# murdock_mcu_v2.net
KiCad netlist of a schematic drawn in EAGLE
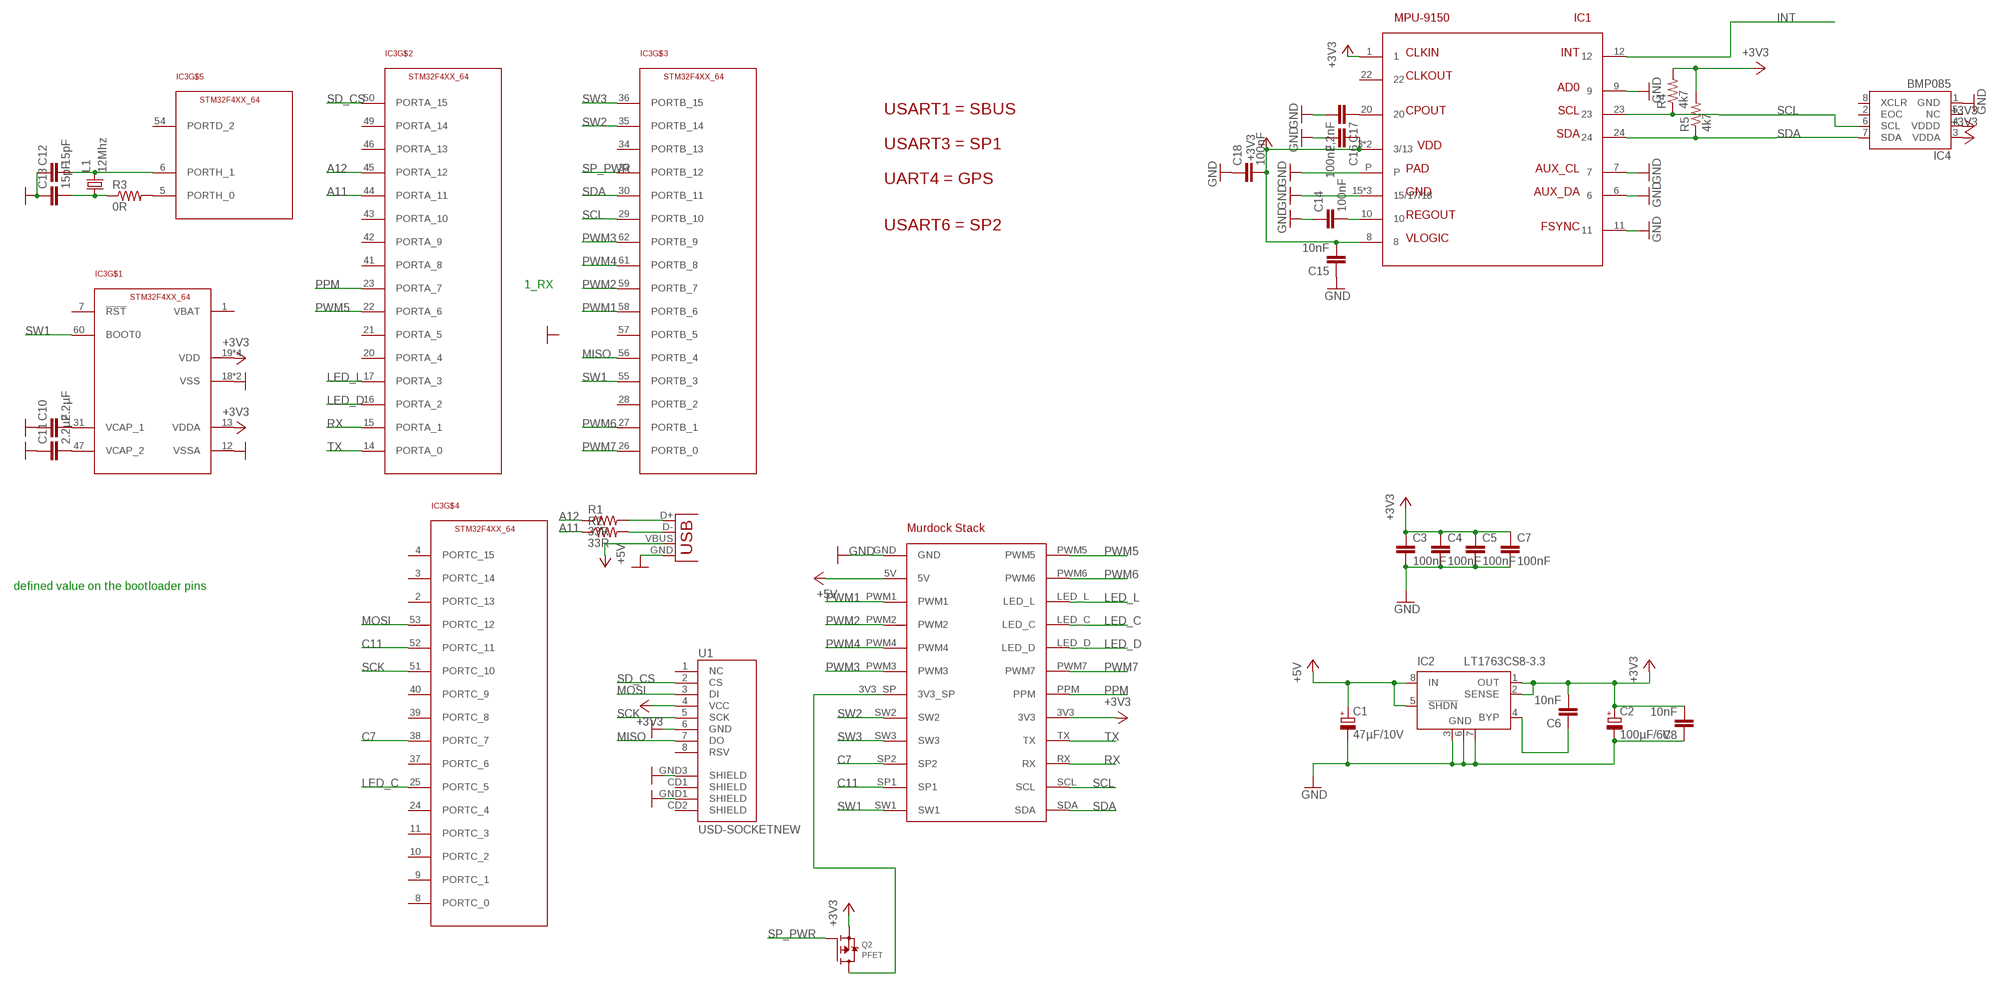
[diagram p0: schematic, sheet 1]

(export (version "E")
  (design (tool "Eeschema 10.0.6"))
  (components
    (comp (ref "C1")
      (value "47µF/10V")
      (footprint "eagle-import:SMC_D")
      (libsource (lib "eagle-import") (part "CPOL-EUSMCD"))
    )
    (comp (ref "C2")
      (value "100µF/6V")
      (footprint "eagle-import:SMC_D")
      (libsource (lib "eagle-import") (part "CPOL-EUSMCD"))
    )
    (comp (ref "C3")
      (value "100nF")
      (footprint "eagle-import:0402-CAP")
      (libsource (lib "eagle-import") (part "SparkFun-Capacitors_CAP0402-CAP"))
    )
    (comp (ref "C4")
      (value "100nF")
      (footprint "eagle-import:0402-CAP")
      (libsource (lib "eagle-import") (part "SparkFun-Capacitors_CAP0402-CAP"))
    )
    (comp (ref "C5")
      (value "100nF")
      (footprint "eagle-import:0402-CAP")
      (libsource (lib "eagle-import") (part "SparkFun-Capacitors_CAP0402-CAP"))
    )
    (comp (ref "C6")
      (value "10nF")
      (footprint "eagle-import:C0402")
      (libsource (lib "eagle-import") (part "C-EUC0402"))
    )
    (comp (ref "C7")
      (value "100nF")
      (footprint "eagle-import:0402-CAP")
      (libsource (lib "eagle-import") (part "SparkFun-Capacitors_CAP0402-CAP"))
    )
    (comp (ref "C8")
      (value "10nF")
      (footprint "eagle-import:C0402")
      (libsource (lib "eagle-import") (part "C-EUC0402"))
    )
    (comp (ref "C10")
      (value "2.2µF")
      (footprint "eagle-import:0805")
      (libsource (lib "eagle-import") (part "SparkFun-Capacitors_CAP0805"))
    )
    (comp (ref "C11")
      (value "2.2µF")
      (footprint "eagle-import:0805")
      (libsource (lib "eagle-import") (part "SparkFun-Capacitors_CAP0805"))
    )
    (comp (ref "C12")
      (value "15pF")
      (footprint "eagle-import:0402-CAP")
      (libsource (lib "eagle-import") (part "SparkFun-Capacitors_CAP0402-CAP"))
    )
    (comp (ref "C13")
      (value "15pF")
      (footprint "eagle-import:0402-CAP")
      (libsource (lib "eagle-import") (part "SparkFun-Capacitors_CAP0402-CAP"))
    )
    (comp (ref "C14")
      (value "100nF")
      (footprint "eagle-import:0402-CAP")
      (libsource (lib "eagle-import") (part "CAP0402-CAP"))
    )
    (comp (ref "C15")
      (value "10nF")
      (footprint "eagle-import:0402-CAP")
      (libsource (lib "eagle-import") (part "CAP0402-CAP"))
    )
    (comp (ref "C16")
      (value "100nF")
      (footprint "eagle-import:0402-CAP")
      (libsource (lib "eagle-import") (part "CAP0402-CAP"))
    )
    (comp (ref "C17")
      (value "2,2nF")
      (footprint "eagle-import:0402-CAP")
      (libsource (lib "eagle-import") (part "CAP0402-CAP"))
    )
    (comp (ref "C18")
      (value "100nF")
      (footprint "eagle-import:0402-CAP")
      (libsource (lib "eagle-import") (part "CAP0402-CAP"))
    )
    (comp (ref "IC1")
      (value "MPU-9150")
      (footprint "eagle-import:QFN24")
      (libsource (lib "eagle-import") (part "MPU-9150"))
    )
    (comp (ref "IC2")
      (value "LT1763CS8-3.3")
      (footprint "eagle-import:SOIC8")
      (libsource (lib "eagle-import") (part "LT1763CS8-3.3"))
    )
    (comp (ref "IC3")
      (value "STM32F4XX_64")
      (footprint "eagle-import:TQFP64")
      (libsource (lib "eagle-import") (part "STM32F4XX_64"))
    )
    (comp (ref "IC4")
      (value "BMP085")
      (footprint "eagle-import:BMP085")
      (libsource (lib "eagle-import") (part "BMP085"))
    )
    (comp (ref "L1")
      (value "12Mhz")
      (footprint "eagle-import:X22")
      (libsource (lib "eagle-import") (part "X22-OSCILLATOR"))
    )
    (comp (ref "Q2")
      (value "PFET")
      (footprint "eagle-import:SOT23-R")
      (libsource (lib "eagle-import") (part "MOSFET-P"))
    )
    (comp (ref "R1")
      (value "33R")
      (footprint "eagle-import:0402-RES")
      (libsource (lib "eagle-import") (part "SparkFun-Resistors_RESISTOR0402-RES"))
    )
    (comp (ref "R2")
      (value "33R")
      (footprint "eagle-import:0402-RES")
      (libsource (lib "eagle-import") (part "SparkFun-Resistors_RESISTOR0402-RES"))
    )
    (comp (ref "R3")
      (value "0R")
      (footprint "eagle-import:0402-RES")
      (libsource (lib "eagle-import") (part "SparkFun-Resistors_RESISTOR0402-RES"))
    )
    (comp (ref "R4")
      (value "4k7")
      (footprint "eagle-import:0402-RES")
      (libsource (lib "eagle-import") (part "RESISTOR0402-RES"))
    )
    (comp (ref "R5")
      (value "4k7")
      (footprint "eagle-import:0402-RES")
      (libsource (lib "eagle-import") (part "RESISTOR0402-RES"))
    )
    (comp (ref "U1")
      (value "USD-SOCKETNEW")
      (footprint "eagle-import:MICRO-SD-SOCKET-PP")
      (libsource (lib "eagle-import") (part "USD-SOCKETNEW"))
    )
    (comp (ref "X1")
      (value "USBSMD")
      (footprint "eagle-import:USB-MINIB")
      (libsource (lib "eagle-import") (part "USBSMD"))
    )
    (comp (ref "X2")
      (value "MURDOCK_STACK")
      (footprint "eagle-import:MURDOCK_STACK")
      (libsource (lib "eagle-import") (part "MURDOCK_STACK"))
    )
  )
  (nets
    (net (code "1") (name "+3V3") (class "Default")
      (node (ref "C15") (pin "2") (pinfunction "2_2") (pintype "passive"))
      (node (ref "C16") (pin "1") (pinfunction "1_1") (pintype "passive"))
      (node (ref "C18") (pin "2") (pinfunction "2_2") (pintype "passive"))
      (node (ref "C2") (pin "+") (pinfunction "+_+") (pintype "passive"))
      (node (ref "C3") (pin "1") (pinfunction "1_1") (pintype "passive"))
      (node (ref "C4") (pin "1") (pinfunction "1_1") (pintype "passive"))
      (node (ref "C5") (pin "1") (pinfunction "1_1") (pintype "passive"))
      (node (ref "C6") (pin "2") (pinfunction "2_2") (pintype "passive"))
      (node (ref "C7") (pin "1") (pinfunction "1_1") (pintype "passive"))
      (node (ref "C8") (pin "2") (pinfunction "2_2") (pintype "passive"))
      (node (ref "IC1") (pin "1") (pinfunction "1_1") (pintype "bidirectional"))
      (node (ref "IC1") (pin "13") (pinfunction "3/13_13") (pintype "bidirectional"))
      (node (ref "IC1") (pin "3") (pinfunction "3/13_3") (pintype "bidirectional"))
      (node (ref "IC1") (pin "8") (pinfunction "8_8") (pintype "bidirectional"))
      (node (ref "IC2") (pin "1") (pinfunction "OUT_1") (pintype "passive"))
      (node (ref "IC2") (pin "2") (pinfunction "SENSE_2") (pintype "input"))
      (node (ref "IC3") (pin "13") (pinfunction "VDDA_13") (pintype "bidirectional"))
      (node (ref "IC3") (pin "19") (pinfunction "VDD_19") (pintype "bidirectional"))
      (node (ref "IC3") (pin "32") (pinfunction "VDD_32") (pintype "bidirectional"))
      (node (ref "IC3") (pin "48") (pinfunction "VDD_48") (pintype "bidirectional"))
      (node (ref "IC3") (pin "64") (pinfunction "VDD_64") (pintype "bidirectional"))
      (node (ref "IC4") (pin "3") (pinfunction "VDDA_3") (pintype "power_in"))
      (node (ref "IC4") (pin "4") (pinfunction "VDDD_4") (pintype "power_in"))
      (node (ref "Q2") (pin "2") (pinfunction "S_2") (pintype "passive"))
      (node (ref "R4") (pin "2") (pinfunction "2_2") (pintype "passive"))
      (node (ref "R5") (pin "2") (pinfunction "2_2") (pintype "passive"))
      (node (ref "U1") (pin "4") (pinfunction "VCC_4") (pintype "bidirectional"))
      (node (ref "X2") (pin "3V3") (pinfunction "3V3_3V3") (pintype "bidirectional"))
    )
    (net (code "2") (name "+5V") (class "Default")
      (node (ref "C1") (pin "+") (pinfunction "+_+") (pintype "passive"))
      (node (ref "IC2") (pin "5") (pinfunction "~{SHDN}_5") (pintype "input"))
      (node (ref "IC2") (pin "8") (pinfunction "IN_8") (pintype "input"))
      (node (ref "X1") (pin "VBUS") (pinfunction "VBUS_VBUS") (pintype "bidirectional"))
      (node (ref "X2") (pin "5V") (pinfunction "5V_5V") (pintype "bidirectional"))
    )
    (net (code "3") (name "/A11") (class "Default")
      (node (ref "IC3") (pin "44") (pinfunction "PORTA_11_44") (pintype "bidirectional"))
      (node (ref "R2") (pin "1") (pinfunction "1_1") (pintype "passive"))
    )
    (net (code "4") (name "/A12") (class "Default")
      (node (ref "IC3") (pin "45") (pinfunction "PORTA_12_45") (pintype "bidirectional"))
      (node (ref "R1") (pin "1") (pinfunction "1_1") (pintype "passive"))
    )
    (net (code "5") (name "/C7") (class "Default")
      (node (ref "IC3") (pin "38") (pinfunction "PORTC_7_38") (pintype "bidirectional"))
      (node (ref "X2") (pin "SP2") (pinfunction "SP2_SP2") (pintype "bidirectional"))
    )
    (net (code "6") (name "/C11") (class "Default")
      (node (ref "IC3") (pin "52") (pinfunction "PORTC_11_52") (pintype "bidirectional"))
      (node (ref "X2") (pin "SP1") (pinfunction "SP1_SP1") (pintype "bidirectional"))
    )
    (net (code "7") (name "/INT") (class "Default")
      (node (ref "IC1") (pin "12") (pinfunction "12_12") (pintype "bidirectional"))
    )
    (net (code "8") (name "/LED_C") (class "Default")
      (node (ref "IC3") (pin "25") (pinfunction "PORTC_5_25") (pintype "bidirectional"))
      (node (ref "X2") (pin "LED_C") (pinfunction "LED_C_LED_C") (pintype "bidirectional"))
    )
    (net (code "9") (name "/LED_D") (class "Default")
      (node (ref "IC3") (pin "16") (pinfunction "PORTA_2_16") (pintype "bidirectional"))
      (node (ref "X2") (pin "LED_D") (pinfunction "LED_D_LED_D") (pintype "bidirectional"))
    )
    (net (code "10") (name "/LED_L") (class "Default")
      (node (ref "IC3") (pin "17") (pinfunction "PORTA_3_17") (pintype "bidirectional"))
      (node (ref "X2") (pin "LED_L") (pinfunction "LED_L_LED_L") (pintype "bidirectional"))
    )
    (net (code "11") (name "/MISO") (class "Default")
      (node (ref "IC3") (pin "56") (pinfunction "PORTB_4_56") (pintype "bidirectional"))
      (node (ref "U1") (pin "7") (pinfunction "DO_7") (pintype "bidirectional"))
    )
    (net (code "12") (name "/MOSI") (class "Default")
      (node (ref "IC3") (pin "53") (pinfunction "PORTC_12_53") (pintype "bidirectional"))
      (node (ref "U1") (pin "3") (pinfunction "DI_3") (pintype "bidirectional"))
    )
    (net (code "13") (name "/PPM") (class "Default")
      (node (ref "IC3") (pin "23") (pinfunction "PORTA_7_23") (pintype "bidirectional"))
      (node (ref "X2") (pin "PPM") (pinfunction "PPM_PPM") (pintype "bidirectional"))
    )
    (net (code "14") (name "/PWM1") (class "Default")
      (node (ref "IC3") (pin "58") (pinfunction "PORTB_6_58") (pintype "bidirectional"))
      (node (ref "X2") (pin "PWM1") (pinfunction "PWM1_PWM1") (pintype "bidirectional"))
    )
    (net (code "15") (name "/PWM2") (class "Default")
      (node (ref "IC3") (pin "59") (pinfunction "PORTB_7_59") (pintype "bidirectional"))
      (node (ref "X2") (pin "PWM2") (pinfunction "PWM2_PWM2") (pintype "bidirectional"))
    )
    (net (code "16") (name "/PWM3") (class "Default")
      (node (ref "IC3") (pin "62") (pinfunction "PORTB_9_62") (pintype "bidirectional"))
      (node (ref "X2") (pin "PWM3") (pinfunction "PWM3_PWM3") (pintype "bidirectional"))
    )
    (net (code "17") (name "/PWM4") (class "Default")
      (node (ref "IC3") (pin "61") (pinfunction "PORTB_8_61") (pintype "bidirectional"))
      (node (ref "X2") (pin "PWM4") (pinfunction "PWM4_PWM4") (pintype "bidirectional"))
    )
    (net (code "18") (name "/PWM5") (class "Default")
      (node (ref "IC3") (pin "22") (pinfunction "PORTA_6_22") (pintype "bidirectional"))
      (node (ref "X2") (pin "PWM5") (pinfunction "PWM5_PWM5") (pintype "bidirectional"))
    )
    (net (code "19") (name "/PWM6") (class "Default")
      (node (ref "IC3") (pin "27") (pinfunction "PORTB_1_27") (pintype "bidirectional"))
      (node (ref "X2") (pin "PWM6") (pinfunction "PWM6_PWM6") (pintype "bidirectional"))
    )
    (net (code "20") (name "/PWM7") (class "Default")
      (node (ref "IC3") (pin "26") (pinfunction "PORTB_0_26") (pintype "bidirectional"))
      (node (ref "X2") (pin "PWM7") (pinfunction "PWM7_PWM7") (pintype "bidirectional"))
    )
    (net (code "21") (name "/RX") (class "Default")
      (node (ref "IC3") (pin "15") (pinfunction "PORTA_1_15") (pintype "bidirectional"))
      (node (ref "X2") (pin "RX") (pinfunction "RX_RX") (pintype "bidirectional"))
    )
    (net (code "22") (name "/SCK") (class "Default")
      (node (ref "IC3") (pin "51") (pinfunction "PORTC_10_51") (pintype "bidirectional"))
      (node (ref "U1") (pin "5") (pinfunction "SCK_5") (pintype "bidirectional"))
    )
    (net (code "23") (name "/SCL") (class "Default")
      (node (ref "IC1") (pin "23") (pinfunction "23_23") (pintype "bidirectional"))
      (node (ref "IC3") (pin "29") (pinfunction "PORTB_10_29") (pintype "bidirectional"))
      (node (ref "IC4") (pin "6") (pinfunction "SCL_6") (pintype "input"))
      (node (ref "R4") (pin "1") (pinfunction "1_1") (pintype "passive"))
      (node (ref "X2") (pin "SCL") (pinfunction "SCL_SCL") (pintype "bidirectional"))
    )
    (net (code "24") (name "/SDA") (class "Default")
      (node (ref "IC1") (pin "24") (pinfunction "24_24") (pintype "bidirectional"))
      (node (ref "IC3") (pin "30") (pinfunction "PORTB_11_30") (pintype "bidirectional"))
      (node (ref "IC4") (pin "7") (pinfunction "SDA_7") (pintype "bidirectional"))
      (node (ref "R5") (pin "1") (pinfunction "1_1") (pintype "passive"))
      (node (ref "X2") (pin "SDA") (pinfunction "SDA_SDA") (pintype "bidirectional"))
    )
    (net (code "25") (name "/SD_CS") (class "Default")
      (node (ref "IC3") (pin "50") (pinfunction "PORTA_15_50") (pintype "bidirectional"))
      (node (ref "U1") (pin "2") (pinfunction "CS_2") (pintype "bidirectional"))
    )
    (net (code "26") (name "/SP_PWR") (class "Default")
      (node (ref "IC3") (pin "33") (pinfunction "PORTB_12_33") (pintype "bidirectional"))
      (node (ref "Q2") (pin "1") (pinfunction "G_1") (pintype "passive"))
    )
    (net (code "27") (name "/SW1") (class "Default")
      (node (ref "IC3") (pin "55") (pinfunction "PORTB_3_55") (pintype "bidirectional"))
      (node (ref "IC3") (pin "60") (pinfunction "BOOT0_60") (pintype "bidirectional"))
      (node (ref "X2") (pin "SW1") (pinfunction "SW1_SW1") (pintype "bidirectional"))
    )
    (net (code "28") (name "/SW2") (class "Default")
      (node (ref "IC3") (pin "35") (pinfunction "PORTB_14_35") (pintype "bidirectional"))
      (node (ref "X2") (pin "SW2") (pinfunction "SW2_SW2") (pintype "bidirectional"))
    )
    (net (code "29") (name "/SW3") (class "Default")
      (node (ref "IC3") (pin "36") (pinfunction "PORTB_15_36") (pintype "bidirectional"))
      (node (ref "X2") (pin "SW3") (pinfunction "SW3_SW3") (pintype "bidirectional"))
    )
    (net (code "30") (name "/TX") (class "Default")
      (node (ref "IC3") (pin "14") (pinfunction "PORTA_0_14") (pintype "bidirectional"))
      (node (ref "X2") (pin "TX") (pinfunction "TX_TX") (pintype "bidirectional"))
    )
    (net (code "31") (name "GND") (class "Default")
      (node (ref "C1") (pin "-") (pinfunction "-_-") (pintype "passive"))
      (node (ref "C10") (pin "1") (pinfunction "1_1") (pintype "passive"))
      (node (ref "C11") (pin "1") (pinfunction "1_1") (pintype "passive"))
      (node (ref "C12") (pin "1") (pinfunction "1_1") (pintype "passive"))
      (node (ref "C13") (pin "1") (pinfunction "1_1") (pintype "passive"))
      (node (ref "C14") (pin "1") (pinfunction "1_1") (pintype "passive"))
      (node (ref "C15") (pin "1") (pinfunction "1_1") (pintype "passive"))
      (node (ref "C16") (pin "2") (pinfunction "2_2") (pintype "passive"))
      (node (ref "C17") (pin "2") (pinfunction "2_2") (pintype "passive"))
      (node (ref "C18") (pin "1") (pinfunction "1_1") (pintype "passive"))
      (node (ref "C2") (pin "-") (pinfunction "-_-") (pintype "passive"))
      (node (ref "C3") (pin "2") (pinfunction "2_2") (pintype "passive"))
      (node (ref "C4") (pin "2") (pinfunction "2_2") (pintype "passive"))
      (node (ref "C5") (pin "2") (pinfunction "2_2") (pintype "passive"))
      (node (ref "C7") (pin "2") (pinfunction "2_2") (pintype "passive"))
      (node (ref "C8") (pin "1") (pinfunction "1_1") (pintype "passive"))
      (node (ref "IC1") (pin "11") (pinfunction "11_11") (pintype "bidirectional"))
      (node (ref "IC1") (pin "15") (pinfunction "15/17/18_15") (pintype "bidirectional"))
      (node (ref "IC1") (pin "17") (pinfunction "15/17/18_17") (pintype "bidirectional"))
      (node (ref "IC1") (pin "18") (pinfunction "15/17/18_18") (pintype "bidirectional"))
      (node (ref "IC1") (pin "6") (pinfunction "6_6") (pintype "bidirectional"))
      (node (ref "IC1") (pin "7") (pinfunction "7_7") (pintype "bidirectional"))
      (node (ref "IC1") (pin "9") (pinfunction "9_9") (pintype "bidirectional"))
      (node (ref "IC1") (pin "P") (pinfunction "P_P") (pintype "bidirectional"))
      (node (ref "IC2") (pin "3") (pinfunction "GND_3") (pintype "power_in"))
      (node (ref "IC2") (pin "6") (pinfunction "GND_6") (pintype "power_in"))
      (node (ref "IC2") (pin "7") (pinfunction "GND_7") (pintype "power_in"))
      (node (ref "IC3") (pin "12") (pinfunction "VSSA_12") (pintype "bidirectional"))
      (node (ref "IC3") (pin "18") (pinfunction "VSS_18") (pintype "bidirectional"))
      (node (ref "IC3") (pin "63") (pinfunction "VSS_63") (pintype "bidirectional"))
      (node (ref "IC4") (pin "1") (pinfunction "GND_1") (pintype "power_in"))
      (node (ref "U1") (pin "6") (pinfunction "GND_6") (pintype "bidirectional"))
      (node (ref "U1") (pin "GND1") (pinfunction "SHIELD_GND1") (pintype "bidirectional"))
      (node (ref "U1") (pin "GND3") (pinfunction "SHIELD_GND3") (pintype "bidirectional"))
      (node (ref "X1") (pin "GND") (pinfunction "GND_GND") (pintype "bidirectional"))
      (node (ref "X2") (pin "GND") (pinfunction "GND_GND") (pintype "bidirectional"))
    )
    (net (code "32") (name "Net-(C13-Pad2)") (class "Default")
      (node (ref "C13") (pin "2") (pinfunction "2_2") (pintype "passive"))
      (node (ref "L1") (pin "1") (pinfunction "1_1") (pintype "passive"))
      (node (ref "R3") (pin "1") (pinfunction "1_1") (pintype "passive"))
    )
    (net (code "33") (name "Net-(C14-Pad2)") (class "Default")
      (node (ref "C14") (pin "2") (pinfunction "2_2") (pintype "passive"))
      (node (ref "IC1") (pin "10") (pinfunction "10_10") (pintype "bidirectional"))
    )
    (net (code "34") (name "Net-(C17-Pad1)") (class "Default")
      (node (ref "C17") (pin "1") (pinfunction "1_1") (pintype "passive"))
      (node (ref "IC1") (pin "20") (pinfunction "20_20") (pintype "bidirectional"))
    )
    (net (code "35") (name "Net-(IC2-BYP)") (class "Default")
      (node (ref "C6") (pin "1") (pinfunction "1_1") (pintype "passive"))
      (node (ref "IC2") (pin "4") (pinfunction "BYP_4") (pintype "input"))
    )
    (net (code "36") (name "Net-(IC3A-VCAP_1)") (class "Default")
      (node (ref "C10") (pin "2") (pinfunction "2_2") (pintype "passive"))
      (node (ref "IC3") (pin "31") (pinfunction "VCAP_1_31") (pintype "bidirectional"))
    )
    (net (code "37") (name "Net-(IC3A-VCAP_2)") (class "Default")
      (node (ref "C11") (pin "2") (pinfunction "2_2") (pintype "passive"))
      (node (ref "IC3") (pin "47") (pinfunction "VCAP_2_47") (pintype "bidirectional"))
    )
    (net (code "38") (name "Net-(IC3E-PORTH_0)") (class "Default")
      (node (ref "IC3") (pin "5") (pinfunction "PORTH_0_5") (pintype "bidirectional"))
      (node (ref "R3") (pin "2") (pinfunction "2_2") (pintype "passive"))
    )
    (net (code "39") (name "Net-(IC3E-PORTH_1)") (class "Default")
      (node (ref "C12") (pin "2") (pinfunction "2_2") (pintype "passive"))
      (node (ref "IC3") (pin "6") (pinfunction "PORTH_1_6") (pintype "bidirectional"))
      (node (ref "L1") (pin "3") (pinfunction "2_3") (pintype "passive"))
    )
    (net (code "40") (name "Net-(Q2-D)") (class "Default")
      (node (ref "Q2") (pin "3") (pinfunction "D_3") (pintype "passive"))
      (node (ref "X2") (pin "3V3_SP") (pinfunction "3V3_SP_3V3_SP") (pintype "bidirectional"))
    )
    (net (code "41") (name "Net-(R1-Pad2)") (class "Default")
      (node (ref "R1") (pin "2") (pinfunction "2_2") (pintype "passive"))
      (node (ref "X1") (pin "D+") (pinfunction "D+_D+") (pintype "bidirectional"))
    )
    (net (code "42") (name "Net-(R2-Pad2)") (class "Default")
      (node (ref "R2") (pin "2") (pinfunction "2_2") (pintype "passive"))
      (node (ref "X1") (pin "D-") (pinfunction "D-_D-") (pintype "bidirectional"))
    )
    (net (code "43") (name "unconnected-(IC1-Pad22)") (class "Default")
      (node (ref "IC1") (pin "22") (pinfunction "22_22") (pintype "bidirectional"))
    )
    (net (code "44") (name "unconnected-(IC3A-VBAT-Pad1)") (class "Default")
      (node (ref "IC3") (pin "1") (pinfunction "VBAT_1") (pintype "bidirectional"))
    )
    (net (code "45") (name "unconnected-(IC3A-~{RST}-Pad7)") (class "Default")
      (node (ref "IC3") (pin "7") (pinfunction "~{RST}_7") (pintype "bidirectional"))
    )
    (net (code "46") (name "unconnected-(IC3B-PORTA_4-Pad20)") (class "Default")
      (node (ref "IC3") (pin "20") (pinfunction "PORTA_4_20") (pintype "bidirectional"))
    )
    (net (code "47") (name "unconnected-(IC3B-PORTA_5-Pad21)") (class "Default")
      (node (ref "IC3") (pin "21") (pinfunction "PORTA_5_21") (pintype "bidirectional"))
    )
    (net (code "48") (name "unconnected-(IC3B-PORTA_8-Pad41)") (class "Default")
      (node (ref "IC3") (pin "41") (pinfunction "PORTA_8_41") (pintype "bidirectional"))
    )
    (net (code "49") (name "unconnected-(IC3B-PORTA_9-Pad42)") (class "Default")
      (node (ref "IC3") (pin "42") (pinfunction "PORTA_9_42") (pintype "bidirectional"))
    )
    (net (code "50") (name "unconnected-(IC3B-PORTA_10-Pad43)") (class "Default")
      (node (ref "IC3") (pin "43") (pinfunction "PORTA_10_43") (pintype "bidirectional"))
    )
    (net (code "51") (name "unconnected-(IC3B-PORTA_13-Pad46)") (class "Default")
      (node (ref "IC3") (pin "46") (pinfunction "PORTA_13_46") (pintype "bidirectional"))
    )
    (net (code "52") (name "unconnected-(IC3B-PORTA_14-Pad49)") (class "Default")
      (node (ref "IC3") (pin "49") (pinfunction "PORTA_14_49") (pintype "bidirectional"))
    )
    (net (code "53") (name "unconnected-(IC3C-PORTB_2-Pad28)") (class "Default")
      (node (ref "IC3") (pin "28") (pinfunction "PORTB_2_28") (pintype "bidirectional"))
    )
    (net (code "54") (name "unconnected-(IC3C-PORTB_5-Pad57)") (class "Default")
      (node (ref "IC3") (pin "57") (pinfunction "PORTB_5_57") (pintype "bidirectional"))
    )
    (net (code "55") (name "unconnected-(IC3C-PORTB_13-Pad34)") (class "Default")
      (node (ref "IC3") (pin "34") (pinfunction "PORTB_13_34") (pintype "bidirectional"))
    )
    (net (code "56") (name "unconnected-(IC3D-PORTC_0-Pad8)") (class "Default")
      (node (ref "IC3") (pin "8") (pinfunction "PORTC_0_8") (pintype "bidirectional"))
    )
    (net (code "57") (name "unconnected-(IC3D-PORTC_1-Pad9)") (class "Default")
      (node (ref "IC3") (pin "9") (pinfunction "PORTC_1_9") (pintype "bidirectional"))
    )
    (net (code "58") (name "unconnected-(IC3D-PORTC_2-Pad10)") (class "Default")
      (node (ref "IC3") (pin "10") (pinfunction "PORTC_2_10") (pintype "bidirectional"))
    )
    (net (code "59") (name "unconnected-(IC3D-PORTC_3-Pad11)") (class "Default")
      (node (ref "IC3") (pin "11") (pinfunction "PORTC_3_11") (pintype "bidirectional"))
    )
    (net (code "60") (name "unconnected-(IC3D-PORTC_4-Pad24)") (class "Default")
      (node (ref "IC3") (pin "24") (pinfunction "PORTC_4_24") (pintype "bidirectional"))
    )
    (net (code "61") (name "unconnected-(IC3D-PORTC_6-Pad37)") (class "Default")
      (node (ref "IC3") (pin "37") (pinfunction "PORTC_6_37") (pintype "bidirectional"))
    )
    (net (code "62") (name "unconnected-(IC3D-PORTC_8-Pad39)") (class "Default")
      (node (ref "IC3") (pin "39") (pinfunction "PORTC_8_39") (pintype "bidirectional"))
    )
    (net (code "63") (name "unconnected-(IC3D-PORTC_9-Pad40)") (class "Default")
      (node (ref "IC3") (pin "40") (pinfunction "PORTC_9_40") (pintype "bidirectional"))
    )
    (net (code "64") (name "unconnected-(IC3D-PORTC_13-Pad2)") (class "Default")
      (node (ref "IC3") (pin "2") (pinfunction "PORTC_13_2") (pintype "bidirectional"))
    )
    (net (code "65") (name "unconnected-(IC3D-PORTC_14-Pad3)") (class "Default")
      (node (ref "IC3") (pin "3") (pinfunction "PORTC_14_3") (pintype "bidirectional"))
    )
    (net (code "66") (name "unconnected-(IC3D-PORTC_15-Pad4)") (class "Default")
      (node (ref "IC3") (pin "4") (pinfunction "PORTC_15_4") (pintype "bidirectional"))
    )
    (net (code "67") (name "unconnected-(IC3E-PORTD_2-Pad54)") (class "Default")
      (node (ref "IC3") (pin "54") (pinfunction "PORTD_2_54") (pintype "bidirectional"))
    )
    (net (code "68") (name "unconnected-(IC4-EOC-Pad2)") (class "Default")
      (node (ref "IC4") (pin "2") (pinfunction "EOC_2") (pintype "output"))
    )
    (net (code "69") (name "unconnected-(IC4-NC-Pad5)") (class "Default")
      (node (ref "IC4") (pin "5") (pinfunction "NC_5") (pintype "bidirectional"))
    )
    (net (code "70") (name "unconnected-(IC4-XCLR-Pad8)") (class "Default")
      (node (ref "IC4") (pin "8") (pinfunction "XCLR_8") (pintype "input"))
    )
    (net (code "71") (name "unconnected-(U1-NC-Pad1)") (class "Default")
      (node (ref "U1") (pin "1") (pinfunction "NC_1") (pintype "bidirectional"))
    )
    (net (code "72") (name "unconnected-(U1-RSV-Pad8)") (class "Default")
      (node (ref "U1") (pin "8") (pinfunction "RSV_8") (pintype "bidirectional"))
    )
    (net (code "73") (name "unconnected-(U1-SHIELD-PadCD1)") (class "Default")
      (node (ref "U1") (pin "CD1") (pinfunction "SHIELD_CD1") (pintype "bidirectional"))
    )
    (net (code "74") (name "unconnected-(U1-SHIELD-PadCD2)") (class "Default")
      (node (ref "U1") (pin "CD2") (pinfunction "SHIELD_CD2") (pintype "bidirectional"))
    )
  )
)
